# Sheet3.net
KiCad netlist of a schematic drawn in Altium Designer
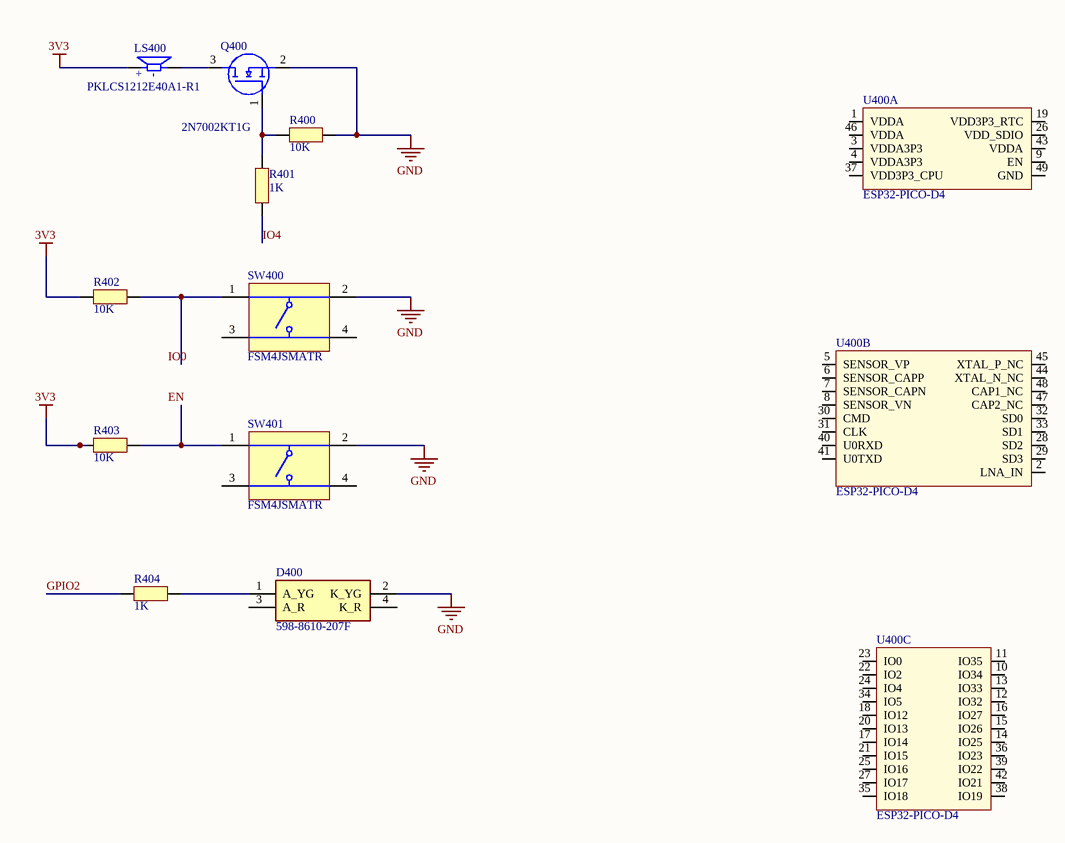
[diagram p0: Sheet3.SchDoc]

(export (version "E")
  (design (tool "Eeschema 10.0.6"))
  (components
    (comp (ref "D400")
      (value "598-8610-207F")
      (footprint "5988610207F")
      (description "Standard LEDs - SMD Red/Green WC 80/50mcd 645/570nm")
      (fields (field (name "MOUSER PART NUMBER") "645-598-8610-207F"))
      (libsource (lib "SCHLibrary") (part "598-8610-207F"))
    )
    (comp (ref "LS400")
      (value "PKLCS1212E40A1-R1")
      (footprint "PCBLibrary:SPKR_PKLCS1212E40A1-R1")
      (description "Buzzers Transducer, Externally Driven Piezo 1.5V 2kHz 70dB @ 1.5V, 10cm Surface Mount Solder Pads")
      (fields (field (name "MF") "Murata Electronics"))
      (libsource (lib "SCHLibrary") (part "PKLCS1212E40A1-R1"))
    )
    (comp (ref "Q400")
      (value "2N7002KT1G")
      (footprint "SOT96P237X111-3N")
      (fields (field (name "MOUSER PART NUMBER") "863-2N7002KT1G"))
      (libsource (lib "SCHLibrary") (part "2N7002KT1G"))
    )
    (comp (ref "R400") (value "10K") (footprint "RESC1005X06N") (libsource (lib "") (part "Resistor_2")))
    (comp (ref "R401")
      (value "1K")
      (footprint "RESC1005X06N")
      (libsource (lib "SCHLibrary") (part "Resistor"))
    )
    (comp (ref "R402") (value "10K") (footprint "RESC1005X06N") (libsource (lib "") (part "Resistor_1")))
    (comp (ref "R403") (value "10K") (footprint "RESC1005X06N") (libsource (lib "") (part "Resistor_1")))
    (comp (ref "R404") (value "1K") (footprint "RESC1005X06N") (libsource (lib "") (part "Resistor_1")))
    (comp (ref "SW400")
      (value "FSM4JSMATR")
      (footprint "TECO-FSM4JSMATR_V")
      (description "Micro Miniature Push Button Switch FSM JSM, 50 mA, -35 to 85 degC, 4-Pin SMD, RoHS, Tape and Reel")
      (fields (field (name "MANUFACTURER") "TE Connectivity"))
      (libsource (lib "SCHLibrary") (part "CMP-2000-07486-1"))
    )
    (comp (ref "SW401")
      (value "FSM4JSMATR")
      (footprint "TECO-FSM4JSMATR_V")
      (description "Micro Miniature Push Button Switch FSM JSM, 50 mA, -35 to 85 degC, 4-Pin SMD, RoHS, Tape and Reel")
      (fields (field (name "MANUFACTURER") "TE Connectivity"))
      (libsource (lib "SCHLibrary") (part "CMP-2000-07486-1"))
    )
    (comp (ref "U400")
      (value "ESP32-PICO-D4")
      (footprint "PQFN50P700X700X104_HS-49N")
      (libsource (lib "SCHLibrary") (part "ESP32"))
    )
  )
  (nets
    (net (code "2") (name "/GPIO2") (class "Default")
      (node (ref "R404") (pin "2") (pinfunction "2_2") (pintype "passive"))
    )
    (net (code "4") (name "/IO4") (class "Default")
      (node (ref "R401") (pin "1") (pinfunction "1_1") (pintype "passive"))
    )
    (net (code "5") (name "3V3") (class "Default")
      (node (ref "LS400") (pin "P") (pinfunction "P_P") (pintype "passive"))
      (node (ref "R402") (pin "2") (pinfunction "2_2") (pintype "passive"))
      (node (ref "R403") (pin "2") (pinfunction "2_2") (pintype "passive"))
    )
    (net (code "6") (name "GND") (class "Default")
      (node (ref "D400") (pin "2") (pinfunction "K_YG_2") (pintype "passive"))
      (node (ref "Q400") (pin "2") (pinfunction "S_2") (pintype "passive"))
      (node (ref "R400") (pin "2") (pinfunction "2_2") (pintype "passive"))
      (node (ref "SW400") (pin "2") (pinfunction "2_2") (pintype "passive"))
      (node (ref "SW401") (pin "2") (pinfunction "2_2") (pintype "passive"))
    )
    (net (code "7") (name "Net-(D400-A_YG)") (class "Default")
      (node (ref "D400") (pin "1") (pinfunction "A_YG_1") (pintype "passive"))
      (node (ref "R404") (pin "1") (pinfunction "1_1") (pintype "passive"))
    )
    (net (code "8") (name "Net-(Q400-D)") (class "Default")
      (node (ref "LS400") (pin "N") (pinfunction "N_N") (pintype "passive"))
      (node (ref "Q400") (pin "3") (pinfunction "D_3") (pintype "passive"))
    )
    (net (code "9") (name "Net-(Q400-G)") (class "Default")
      (node (ref "Q400") (pin "1") (pinfunction "G_1") (pintype "passive"))
      (node (ref "R400") (pin "1") (pinfunction "1_1") (pintype "passive"))
      (node (ref "R401") (pin "2") (pinfunction "2_2") (pintype "passive"))
    )
    (net (code "10") (name "Net-(R402-Pad1)") (class "Default")
      (node (ref "R402") (pin "1") (pinfunction "1_1") (pintype "passive"))
      (node (ref "SW400") (pin "1") (pinfunction "1_1") (pintype "passive"))
    )
    (net (code "11") (name "Net-(R403-Pad1)") (class "Default")
      (node (ref "R403") (pin "1") (pinfunction "1_1") (pintype "passive"))
      (node (ref "SW401") (pin "1") (pinfunction "1_1") (pintype "passive"))
    )
    (net (code "12") (name "unconnected-(D400-A_R-Pad3)") (class "Default")
      (node (ref "D400") (pin "3") (pinfunction "A_R_3") (pintype "passive"))
    )
    (net (code "13") (name "unconnected-(D400-K_R-Pad4)") (class "Default")
      (node (ref "D400") (pin "4") (pinfunction "K_R_4") (pintype "passive"))
    )
    (net (code "14") (name "unconnected-(SW400-Pad3)") (class "Default")
      (node (ref "SW400") (pin "3") (pinfunction "3_3") (pintype "passive"))
    )
    (net (code "15") (name "unconnected-(SW400-Pad4)") (class "Default")
      (node (ref "SW400") (pin "4") (pinfunction "4_4") (pintype "passive"))
    )
    (net (code "16") (name "unconnected-(SW401-Pad3)") (class "Default")
      (node (ref "SW401") (pin "3") (pinfunction "3_3") (pintype "passive"))
    )
    (net (code "17") (name "unconnected-(SW401-Pad4)") (class "Default")
      (node (ref "SW401") (pin "4") (pinfunction "4_4") (pintype "passive"))
    )
    (net (code "18") (name "unconnected-(U400A-EN-Pad9)") (class "Default")
      (node (ref "U400") (pin "9") (pinfunction "EN_9") (pintype "passive"))
    )
    (net (code "19") (name "unconnected-(U400A-GND-Pad49)") (class "Default")
      (node (ref "U400") (pin "49") (pinfunction "GND_49") (pintype "passive"))
    )
    (net (code "20") (name "unconnected-(U400A-VDD3P3_CPU-Pad37)") (class "Default")
      (node (ref "U400") (pin "37") (pinfunction "VDD3P3_CPU_37") (pintype "passive"))
    )
    (net (code "21") (name "unconnected-(U400A-VDD3P3_RTC-Pad19)") (class "Default")
      (node (ref "U400") (pin "19") (pinfunction "VDD3P3_RTC_19") (pintype "passive"))
    )
    (net (code "22") (name "unconnected-(U400A-VDDA-Pad1)") (class "Default")
      (node (ref "U400") (pin "1") (pinfunction "VDDA_1") (pintype "passive"))
    )
    (net (code "23") (name "unconnected-(U400A-VDDA-Pad43)") (class "Default")
      (node (ref "U400") (pin "43") (pinfunction "VDDA_43") (pintype "passive"))
    )
    (net (code "24") (name "unconnected-(U400A-VDDA-Pad46)") (class "Default")
      (node (ref "U400") (pin "46") (pinfunction "VDDA_46") (pintype "passive"))
    )
    (net (code "25") (name "unconnected-(U400A-VDDA3P3-Pad3)") (class "Default")
      (node (ref "U400") (pin "3") (pinfunction "VDDA3P3_3") (pintype "passive"))
    )
    (net (code "26") (name "unconnected-(U400A-VDDA3P3-Pad4)") (class "Default")
      (node (ref "U400") (pin "4") (pinfunction "VDDA3P3_4") (pintype "passive"))
    )
    (net (code "27") (name "unconnected-(U400A-VDD_SDIO-Pad26)") (class "Default")
      (node (ref "U400") (pin "26") (pinfunction "VDD_SDIO_26") (pintype "passive"))
    )
    (net (code "28") (name "unconnected-(U400B-CAP1_NC-Pad48)") (class "Default")
      (node (ref "U400") (pin "48") (pinfunction "CAP1_NC_48") (pintype "passive"))
    )
    (net (code "29") (name "unconnected-(U400B-CAP2_NC-Pad47)") (class "Default")
      (node (ref "U400") (pin "47") (pinfunction "CAP2_NC_47") (pintype "passive"))
    )
    (net (code "30") (name "unconnected-(U400B-CLK-Pad31)") (class "Default")
      (node (ref "U400") (pin "31") (pinfunction "CLK_31") (pintype "passive"))
    )
    (net (code "31") (name "unconnected-(U400B-CMD-Pad30)") (class "Default")
      (node (ref "U400") (pin "30") (pinfunction "CMD_30") (pintype "passive"))
    )
    (net (code "32") (name "unconnected-(U400B-LNA_IN-Pad2)") (class "Default")
      (node (ref "U400") (pin "2") (pinfunction "LNA_IN_2") (pintype "passive"))
    )
    (net (code "33") (name "unconnected-(U400B-SD0-Pad32)") (class "Default")
      (node (ref "U400") (pin "32") (pinfunction "SD0_32") (pintype "passive"))
    )
    (net (code "34") (name "unconnected-(U400B-SD1-Pad33)") (class "Default")
      (node (ref "U400") (pin "33") (pinfunction "SD1_33") (pintype "passive"))
    )
    (net (code "35") (name "unconnected-(U400B-SD2-Pad28)") (class "Default")
      (node (ref "U400") (pin "28") (pinfunction "SD2_28") (pintype "passive"))
    )
    (net (code "36") (name "unconnected-(U400B-SD3-Pad29)") (class "Default")
      (node (ref "U400") (pin "29") (pinfunction "SD3_29") (pintype "passive"))
    )
    (net (code "37") (name "unconnected-(U400B-SENSOR_CAPN-Pad7)") (class "Default")
      (node (ref "U400") (pin "7") (pinfunction "SENSOR_CAPN_7") (pintype "passive"))
    )
    (net (code "38") (name "unconnected-(U400B-SENSOR_CAPP-Pad6)") (class "Default")
      (node (ref "U400") (pin "6") (pinfunction "SENSOR_CAPP_6") (pintype "passive"))
    )
    (net (code "39") (name "unconnected-(U400B-SENSOR_VN-Pad8)") (class "Default")
      (node (ref "U400") (pin "8") (pinfunction "SENSOR_VN_8") (pintype "passive"))
    )
    (net (code "40") (name "unconnected-(U400B-SENSOR_VP-Pad5)") (class "Default")
      (node (ref "U400") (pin "5") (pinfunction "SENSOR_VP_5") (pintype "passive"))
    )
    (net (code "41") (name "unconnected-(U400B-U0RXD-Pad40)") (class "Default")
      (node (ref "U400") (pin "40") (pinfunction "U0RXD_40") (pintype "passive"))
    )
    (net (code "42") (name "unconnected-(U400B-U0TXD-Pad41)") (class "Default")
      (node (ref "U400") (pin "41") (pinfunction "U0TXD_41") (pintype "passive"))
    )
    (net (code "43") (name "unconnected-(U400B-XTAL_N_NC-Pad44)") (class "Default")
      (node (ref "U400") (pin "44") (pinfunction "XTAL_N_NC_44") (pintype "passive"))
    )
    (net (code "44") (name "unconnected-(U400B-XTAL_P_NC-Pad45)") (class "Default")
      (node (ref "U400") (pin "45") (pinfunction "XTAL_P_NC_45") (pintype "passive"))
    )
    (net (code "45") (name "unconnected-(U400C-IO0-Pad23)") (class "Default")
      (node (ref "U400") (pin "23") (pinfunction "IO0_23") (pintype "passive"))
    )
    (net (code "46") (name "unconnected-(U400C-IO2-Pad22)") (class "Default")
      (node (ref "U400") (pin "22") (pinfunction "IO2_22") (pintype "passive"))
    )
    (net (code "47") (name "unconnected-(U400C-IO4-Pad24)") (class "Default")
      (node (ref "U400") (pin "24") (pinfunction "IO4_24") (pintype "passive"))
    )
    (net (code "48") (name "unconnected-(U400C-IO5-Pad34)") (class "Default")
      (node (ref "U400") (pin "34") (pinfunction "IO5_34") (pintype "passive"))
    )
    (net (code "49") (name "unconnected-(U400C-IO12-Pad18)") (class "Default")
      (node (ref "U400") (pin "18") (pinfunction "IO12_18") (pintype "passive"))
    )
    (net (code "50") (name "unconnected-(U400C-IO13-Pad20)") (class "Default")
      (node (ref "U400") (pin "20") (pinfunction "IO13_20") (pintype "passive"))
    )
    (net (code "51") (name "unconnected-(U400C-IO14-Pad17)") (class "Default")
      (node (ref "U400") (pin "17") (pinfunction "IO14_17") (pintype "passive"))
    )
    (net (code "52") (name "unconnected-(U400C-IO15-Pad21)") (class "Default")
      (node (ref "U400") (pin "21") (pinfunction "IO15_21") (pintype "passive"))
    )
    (net (code "53") (name "unconnected-(U400C-IO16-Pad25)") (class "Default")
      (node (ref "U400") (pin "25") (pinfunction "IO16_25") (pintype "passive"))
    )
    (net (code "54") (name "unconnected-(U400C-IO17-Pad27)") (class "Default")
      (node (ref "U400") (pin "27") (pinfunction "IO17_27") (pintype "passive"))
    )
    (net (code "55") (name "unconnected-(U400C-IO18-Pad35)") (class "Default")
      (node (ref "U400") (pin "35") (pinfunction "IO18_35") (pintype "passive"))
    )
    (net (code "56") (name "unconnected-(U400C-IO19-Pad38)") (class "Default")
      (node (ref "U400") (pin "38") (pinfunction "IO19_38") (pintype "passive"))
    )
    (net (code "57") (name "unconnected-(U400C-IO21-Pad42)") (class "Default")
      (node (ref "U400") (pin "42") (pinfunction "IO21_42") (pintype "passive"))
    )
    (net (code "58") (name "unconnected-(U400C-IO22-Pad39)") (class "Default")
      (node (ref "U400") (pin "39") (pinfunction "IO22_39") (pintype "passive"))
    )
    (net (code "59") (name "unconnected-(U400C-IO23-Pad36)") (class "Default")
      (node (ref "U400") (pin "36") (pinfunction "IO23_36") (pintype "passive"))
    )
    (net (code "60") (name "unconnected-(U400C-IO25-Pad14)") (class "Default")
      (node (ref "U400") (pin "14") (pinfunction "IO25_14") (pintype "passive"))
    )
    (net (code "61") (name "unconnected-(U400C-IO26-Pad15)") (class "Default")
      (node (ref "U400") (pin "15") (pinfunction "IO26_15") (pintype "passive"))
    )
    (net (code "62") (name "unconnected-(U400C-IO27-Pad16)") (class "Default")
      (node (ref "U400") (pin "16") (pinfunction "IO27_16") (pintype "passive"))
    )
    (net (code "63") (name "unconnected-(U400C-IO32-Pad12)") (class "Default")
      (node (ref "U400") (pin "12") (pinfunction "IO32_12") (pintype "passive"))
    )
    (net (code "64") (name "unconnected-(U400C-IO33-Pad13)") (class "Default")
      (node (ref "U400") (pin "13") (pinfunction "IO33_13") (pintype "passive"))
    )
    (net (code "65") (name "unconnected-(U400C-IO34-Pad10)") (class "Default")
      (node (ref "U400") (pin "10") (pinfunction "IO34_10") (pintype "passive"))
    )
    (net (code "66") (name "unconnected-(U400C-IO35-Pad11)") (class "Default")
      (node (ref "U400") (pin "11") (pinfunction "IO35_11") (pintype "passive"))
    )
  )
)
